# FEV-60_LED_Panel.net
KiCad netlist of a schematic drawn in Altium Designer
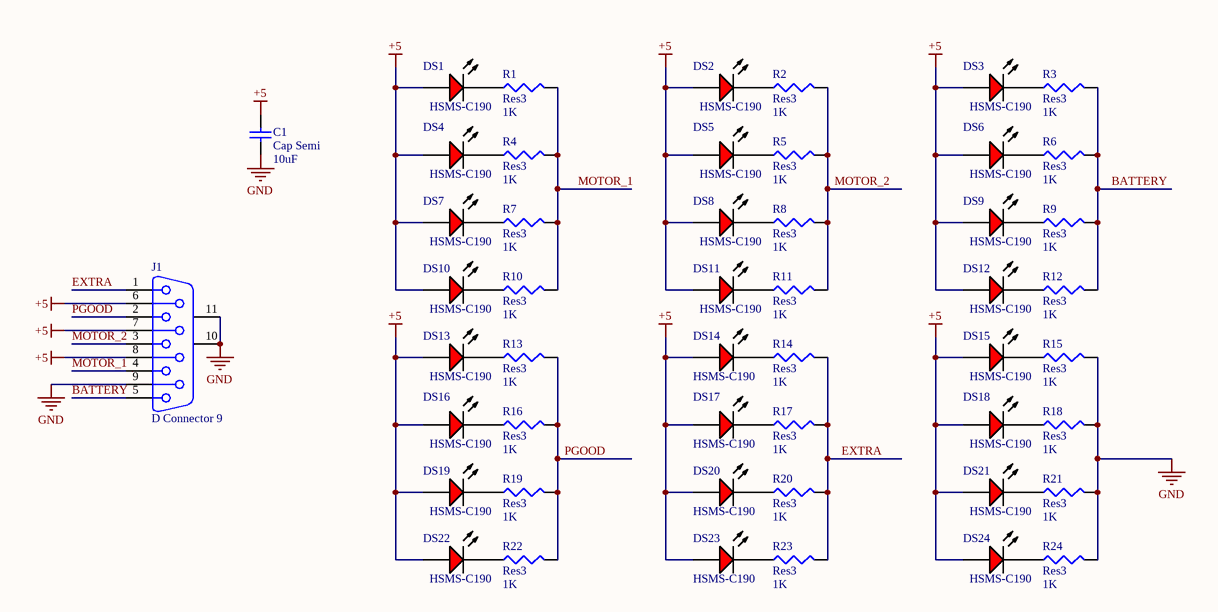
[diagram p0: FEV-60_LED_Panel.SchDoc]

(export (version "E")
  (design (tool "Eeschema 10.0.6"))
  (components
    (comp (ref "C1")
      (value "Cap Semi")
      (footprint "1608[0603]")
      (description "Capacitor (Semiconductor SIM Model)")
      (fields (field (name "ALTIUM_VALUE") "10uF") (field (name "PUBLISHER") "Altium Limited"))
      (libsource (lib "Miscellaneous Devices") (part "Cap Semi"))
    )
    (comp (ref "DS1")
      (value "HSMS-C190")
      (footprint "AVAG-HSMX-C190_V")
      (description "LED Uni-Color Red, 52 mW, 20 mA, -40 to 85 degC, 2-Pin SMD, RoHS, Tape and Reel")
      (fields (field (name "MANUFACTURER") "Avago"))
      (libsource (lib "Altium Content Vault") (part "LED-RED-AK-2"))
    )
    (comp (ref "DS2")
      (value "HSMS-C190")
      (footprint "AVAG-HSMX-C190_V")
      (description "LED Uni-Color Red, 52 mW, 20 mA, -40 to 85 degC, 2-Pin SMD, RoHS, Tape and Reel")
      (fields (field (name "MANUFACTURER") "Avago"))
      (libsource (lib "Altium Content Vault") (part "LED-RED-AK-2"))
    )
    (comp (ref "DS3")
      (value "HSMS-C190")
      (footprint "AVAG-HSMX-C190_V")
      (description "LED Uni-Color Red, 52 mW, 20 mA, -40 to 85 degC, 2-Pin SMD, RoHS, Tape and Reel")
      (fields (field (name "MANUFACTURER") "Avago"))
      (libsource (lib "Altium Content Vault") (part "LED-RED-AK-2"))
    )
    (comp (ref "DS4")
      (value "HSMS-C190")
      (footprint "AVAG-HSMX-C190_V")
      (description "LED Uni-Color Red, 52 mW, 20 mA, -40 to 85 degC, 2-Pin SMD, RoHS, Tape and Reel")
      (fields (field (name "MANUFACTURER") "Avago"))
      (libsource (lib "Altium Content Vault") (part "LED-RED-AK-2"))
    )
    (comp (ref "DS5")
      (value "HSMS-C190")
      (footprint "AVAG-HSMX-C190_V")
      (description "LED Uni-Color Red, 52 mW, 20 mA, -40 to 85 degC, 2-Pin SMD, RoHS, Tape and Reel")
      (fields (field (name "MANUFACTURER") "Avago"))
      (libsource (lib "Altium Content Vault") (part "LED-RED-AK-2"))
    )
    (comp (ref "DS6")
      (value "HSMS-C190")
      (footprint "AVAG-HSMX-C190_V")
      (description "LED Uni-Color Red, 52 mW, 20 mA, -40 to 85 degC, 2-Pin SMD, RoHS, Tape and Reel")
      (fields (field (name "MANUFACTURER") "Avago"))
      (libsource (lib "Altium Content Vault") (part "LED-RED-AK-2"))
    )
    (comp (ref "DS7")
      (value "HSMS-C190")
      (footprint "AVAG-HSMX-C190_V")
      (description "LED Uni-Color Red, 52 mW, 20 mA, -40 to 85 degC, 2-Pin SMD, RoHS, Tape and Reel")
      (fields (field (name "MANUFACTURER") "Avago"))
      (libsource (lib "Altium Content Vault") (part "LED-RED-AK-2"))
    )
    (comp (ref "DS8")
      (value "HSMS-C190")
      (footprint "AVAG-HSMX-C190_V")
      (description "LED Uni-Color Red, 52 mW, 20 mA, -40 to 85 degC, 2-Pin SMD, RoHS, Tape and Reel")
      (fields (field (name "MANUFACTURER") "Avago"))
      (libsource (lib "Altium Content Vault") (part "LED-RED-AK-2"))
    )
    (comp (ref "DS9")
      (value "HSMS-C190")
      (footprint "AVAG-HSMX-C190_V")
      (description "LED Uni-Color Red, 52 mW, 20 mA, -40 to 85 degC, 2-Pin SMD, RoHS, Tape and Reel")
      (fields (field (name "MANUFACTURER") "Avago"))
      (libsource (lib "Altium Content Vault") (part "LED-RED-AK-2"))
    )
    (comp (ref "DS10")
      (value "HSMS-C190")
      (footprint "AVAG-HSMX-C190_V")
      (description "LED Uni-Color Red, 52 mW, 20 mA, -40 to 85 degC, 2-Pin SMD, RoHS, Tape and Reel")
      (fields (field (name "MANUFACTURER") "Avago"))
      (libsource (lib "Altium Content Vault") (part "LED-RED-AK-2"))
    )
    (comp (ref "DS11")
      (value "HSMS-C190")
      (footprint "AVAG-HSMX-C190_V")
      (description "LED Uni-Color Red, 52 mW, 20 mA, -40 to 85 degC, 2-Pin SMD, RoHS, Tape and Reel")
      (fields (field (name "MANUFACTURER") "Avago"))
      (libsource (lib "Altium Content Vault") (part "LED-RED-AK-2"))
    )
    (comp (ref "DS12")
      (value "HSMS-C190")
      (footprint "AVAG-HSMX-C190_V")
      (description "LED Uni-Color Red, 52 mW, 20 mA, -40 to 85 degC, 2-Pin SMD, RoHS, Tape and Reel")
      (fields (field (name "MANUFACTURER") "Avago"))
      (libsource (lib "Altium Content Vault") (part "LED-RED-AK-2"))
    )
    (comp (ref "DS13")
      (value "HSMS-C190")
      (footprint "AVAG-HSMX-C190_V")
      (description "LED Uni-Color Red, 52 mW, 20 mA, -40 to 85 degC, 2-Pin SMD, RoHS, Tape and Reel")
      (fields (field (name "MANUFACTURER") "Avago"))
      (libsource (lib "Altium Content Vault") (part "LED-RED-AK-2"))
    )
    (comp (ref "DS14")
      (value "HSMS-C190")
      (footprint "AVAG-HSMX-C190_V")
      (description "LED Uni-Color Red, 52 mW, 20 mA, -40 to 85 degC, 2-Pin SMD, RoHS, Tape and Reel")
      (fields (field (name "MANUFACTURER") "Avago"))
      (libsource (lib "Altium Content Vault") (part "LED-RED-AK-2"))
    )
    (comp (ref "DS15")
      (value "HSMS-C190")
      (footprint "AVAG-HSMX-C190_V")
      (description "LED Uni-Color Red, 52 mW, 20 mA, -40 to 85 degC, 2-Pin SMD, RoHS, Tape and Reel")
      (fields (field (name "MANUFACTURER") "Avago"))
      (libsource (lib "Altium Content Vault") (part "LED-RED-AK-2"))
    )
    (comp (ref "DS16")
      (value "HSMS-C190")
      (footprint "AVAG-HSMX-C190_V")
      (description "LED Uni-Color Red, 52 mW, 20 mA, -40 to 85 degC, 2-Pin SMD, RoHS, Tape and Reel")
      (fields (field (name "MANUFACTURER") "Avago"))
      (libsource (lib "Altium Content Vault") (part "LED-RED-AK-2"))
    )
    (comp (ref "DS17")
      (value "HSMS-C190")
      (footprint "AVAG-HSMX-C190_V")
      (description "LED Uni-Color Red, 52 mW, 20 mA, -40 to 85 degC, 2-Pin SMD, RoHS, Tape and Reel")
      (fields (field (name "MANUFACTURER") "Avago"))
      (libsource (lib "Altium Content Vault") (part "LED-RED-AK-2"))
    )
    (comp (ref "DS18")
      (value "HSMS-C190")
      (footprint "AVAG-HSMX-C190_V")
      (description "LED Uni-Color Red, 52 mW, 20 mA, -40 to 85 degC, 2-Pin SMD, RoHS, Tape and Reel")
      (fields (field (name "MANUFACTURER") "Avago"))
      (libsource (lib "Altium Content Vault") (part "LED-RED-AK-2"))
    )
    (comp (ref "DS19")
      (value "HSMS-C190")
      (footprint "AVAG-HSMX-C190_V")
      (description "LED Uni-Color Red, 52 mW, 20 mA, -40 to 85 degC, 2-Pin SMD, RoHS, Tape and Reel")
      (fields (field (name "MANUFACTURER") "Avago"))
      (libsource (lib "Altium Content Vault") (part "LED-RED-AK-2"))
    )
    (comp (ref "DS20")
      (value "HSMS-C190")
      (footprint "AVAG-HSMX-C190_V")
      (description "LED Uni-Color Red, 52 mW, 20 mA, -40 to 85 degC, 2-Pin SMD, RoHS, Tape and Reel")
      (fields (field (name "MANUFACTURER") "Avago"))
      (libsource (lib "Altium Content Vault") (part "LED-RED-AK-2"))
    )
    (comp (ref "DS21")
      (value "HSMS-C190")
      (footprint "AVAG-HSMX-C190_V")
      (description "LED Uni-Color Red, 52 mW, 20 mA, -40 to 85 degC, 2-Pin SMD, RoHS, Tape and Reel")
      (fields (field (name "MANUFACTURER") "Avago"))
      (libsource (lib "Altium Content Vault") (part "LED-RED-AK-2"))
    )
    (comp (ref "DS22")
      (value "HSMS-C190")
      (footprint "AVAG-HSMX-C190_V")
      (description "LED Uni-Color Red, 52 mW, 20 mA, -40 to 85 degC, 2-Pin SMD, RoHS, Tape and Reel")
      (fields (field (name "MANUFACTURER") "Avago"))
      (libsource (lib "Altium Content Vault") (part "LED-RED-AK-2"))
    )
    (comp (ref "DS23")
      (value "HSMS-C190")
      (footprint "AVAG-HSMX-C190_V")
      (description "LED Uni-Color Red, 52 mW, 20 mA, -40 to 85 degC, 2-Pin SMD, RoHS, Tape and Reel")
      (fields (field (name "MANUFACTURER") "Avago"))
      (libsource (lib "Altium Content Vault") (part "LED-RED-AK-2"))
    )
    (comp (ref "DS24")
      (value "HSMS-C190")
      (footprint "AVAG-HSMX-C190_V")
      (description "LED Uni-Color Red, 52 mW, 20 mA, -40 to 85 degC, 2-Pin SMD, RoHS, Tape and Reel")
      (fields (field (name "MANUFACTURER") "Avago"))
      (libsource (lib "Altium Content Vault") (part "LED-RED-AK-2"))
    )
    (comp (ref "J1")
      (value "D Connector 9")
      (footprint "DSUB1.385-2H9")
      (description "Receptacle Assembly, 9 Position, Right Angle")
      (fields (field (name "PUBLISHER") "Altium Limited"))
      (libsource (lib "Miscellaneous Connectors") (part "D Connector 9"))
    )
    (comp (ref "R1")
      (value "Res3")
      (footprint "J1-0603")
      (description "Resistor")
      (fields (field (name "ALTIUM_VALUE") "1K") (field (name "PUBLISHER") "Altium Limited"))
      (libsource (lib "Miscellaneous Devices") (part "Res3"))
    )
    (comp (ref "R2")
      (value "Res3")
      (footprint "J1-0603")
      (description "Resistor")
      (fields (field (name "ALTIUM_VALUE") "1K") (field (name "PUBLISHER") "Altium Limited"))
      (libsource (lib "Miscellaneous Devices") (part "Res3"))
    )
    (comp (ref "R3")
      (value "Res3")
      (footprint "J1-0603")
      (description "Resistor")
      (fields (field (name "ALTIUM_VALUE") "1K") (field (name "PUBLISHER") "Altium Limited"))
      (libsource (lib "Miscellaneous Devices") (part "Res3"))
    )
    (comp (ref "R4")
      (value "Res3")
      (footprint "J1-0603")
      (description "Resistor")
      (fields (field (name "ALTIUM_VALUE") "1K") (field (name "PUBLISHER") "Altium Limited"))
      (libsource (lib "Miscellaneous Devices") (part "Res3"))
    )
    (comp (ref "R5")
      (value "Res3")
      (footprint "J1-0603")
      (description "Resistor")
      (fields (field (name "ALTIUM_VALUE") "1K") (field (name "PUBLISHER") "Altium Limited"))
      (libsource (lib "Miscellaneous Devices") (part "Res3"))
    )
    (comp (ref "R6")
      (value "Res3")
      (footprint "J1-0603")
      (description "Resistor")
      (fields (field (name "ALTIUM_VALUE") "1K") (field (name "PUBLISHER") "Altium Limited"))
      (libsource (lib "Miscellaneous Devices") (part "Res3"))
    )
    (comp (ref "R7")
      (value "Res3")
      (footprint "J1-0603")
      (description "Resistor")
      (fields (field (name "ALTIUM_VALUE") "1K") (field (name "PUBLISHER") "Altium Limited"))
      (libsource (lib "Miscellaneous Devices") (part "Res3"))
    )
    (comp (ref "R8")
      (value "Res3")
      (footprint "J1-0603")
      (description "Resistor")
      (fields (field (name "ALTIUM_VALUE") "1K") (field (name "PUBLISHER") "Altium Limited"))
      (libsource (lib "Miscellaneous Devices") (part "Res3"))
    )
    (comp (ref "R9")
      (value "Res3")
      (footprint "J1-0603")
      (description "Resistor")
      (fields (field (name "ALTIUM_VALUE") "1K") (field (name "PUBLISHER") "Altium Limited"))
      (libsource (lib "Miscellaneous Devices") (part "Res3"))
    )
    (comp (ref "R10")
      (value "Res3")
      (footprint "J1-0603")
      (description "Resistor")
      (fields (field (name "ALTIUM_VALUE") "1K") (field (name "PUBLISHER") "Altium Limited"))
      (libsource (lib "Miscellaneous Devices") (part "Res3"))
    )
    (comp (ref "R11")
      (value "Res3")
      (footprint "J1-0603")
      (description "Resistor")
      (fields (field (name "ALTIUM_VALUE") "1K") (field (name "PUBLISHER") "Altium Limited"))
      (libsource (lib "Miscellaneous Devices") (part "Res3"))
    )
    (comp (ref "R12")
      (value "Res3")
      (footprint "J1-0603")
      (description "Resistor")
      (fields (field (name "ALTIUM_VALUE") "1K") (field (name "PUBLISHER") "Altium Limited"))
      (libsource (lib "Miscellaneous Devices") (part "Res3"))
    )
    (comp (ref "R13")
      (value "Res3")
      (footprint "J1-0603")
      (description "Resistor")
      (fields (field (name "ALTIUM_VALUE") "1K") (field (name "PUBLISHER") "Altium Limited"))
      (libsource (lib "Miscellaneous Devices") (part "Res3"))
    )
    (comp (ref "R14")
      (value "Res3")
      (footprint "J1-0603")
      (description "Resistor")
      (fields (field (name "ALTIUM_VALUE") "1K") (field (name "PUBLISHER") "Altium Limited"))
      (libsource (lib "Miscellaneous Devices") (part "Res3"))
    )
    (comp (ref "R15")
      (value "Res3")
      (footprint "J1-0603")
      (description "Resistor")
      (fields (field (name "ALTIUM_VALUE") "1K") (field (name "PUBLISHER") "Altium Limited"))
      (libsource (lib "Miscellaneous Devices") (part "Res3"))
    )
    (comp (ref "R16")
      (value "Res3")
      (footprint "J1-0603")
      (description "Resistor")
      (fields (field (name "ALTIUM_VALUE") "1K") (field (name "PUBLISHER") "Altium Limited"))
      (libsource (lib "Miscellaneous Devices") (part "Res3"))
    )
    (comp (ref "R17")
      (value "Res3")
      (footprint "J1-0603")
      (description "Resistor")
      (fields (field (name "ALTIUM_VALUE") "1K") (field (name "PUBLISHER") "Altium Limited"))
      (libsource (lib "Miscellaneous Devices") (part "Res3"))
    )
    (comp (ref "R18")
      (value "Res3")
      (footprint "J1-0603")
      (description "Resistor")
      (fields (field (name "ALTIUM_VALUE") "1K") (field (name "PUBLISHER") "Altium Limited"))
      (libsource (lib "Miscellaneous Devices") (part "Res3"))
    )
    (comp (ref "R19")
      (value "Res3")
      (footprint "J1-0603")
      (description "Resistor")
      (fields (field (name "ALTIUM_VALUE") "1K") (field (name "PUBLISHER") "Altium Limited"))
      (libsource (lib "Miscellaneous Devices") (part "Res3"))
    )
    (comp (ref "R20")
      (value "Res3")
      (footprint "J1-0603")
      (description "Resistor")
      (fields (field (name "ALTIUM_VALUE") "1K") (field (name "PUBLISHER") "Altium Limited"))
      (libsource (lib "Miscellaneous Devices") (part "Res3"))
    )
    (comp (ref "R21")
      (value "Res3")
      (footprint "J1-0603")
      (description "Resistor")
      (fields (field (name "ALTIUM_VALUE") "1K") (field (name "PUBLISHER") "Altium Limited"))
      (libsource (lib "Miscellaneous Devices") (part "Res3"))
    )
    (comp (ref "R22")
      (value "Res3")
      (footprint "J1-0603")
      (description "Resistor")
      (fields (field (name "ALTIUM_VALUE") "1K") (field (name "PUBLISHER") "Altium Limited"))
      (libsource (lib "Miscellaneous Devices") (part "Res3"))
    )
    (comp (ref "R23")
      (value "Res3")
      (footprint "J1-0603")
      (description "Resistor")
      (fields (field (name "ALTIUM_VALUE") "1K") (field (name "PUBLISHER") "Altium Limited"))
      (libsource (lib "Miscellaneous Devices") (part "Res3"))
    )
    (comp (ref "R24")
      (value "Res3")
      (footprint "J1-0603")
      (description "Resistor")
      (fields (field (name "ALTIUM_VALUE") "1K") (field (name "PUBLISHER") "Altium Limited"))
      (libsource (lib "Miscellaneous Devices") (part "Res3"))
    )
  )
  (nets
    (net (code "1") (name "+5") (class "Default")
      (node (ref "C1") (pin "2") (pinfunction "2_2") (pintype "passive"))
      (node (ref "DS1") (pin "1") (pinfunction "A_1") (pintype "passive"))
      (node (ref "DS10") (pin "1") (pinfunction "A_1") (pintype "passive"))
      (node (ref "DS11") (pin "1") (pinfunction "A_1") (pintype "passive"))
      (node (ref "DS12") (pin "1") (pinfunction "A_1") (pintype "passive"))
      (node (ref "DS13") (pin "1") (pinfunction "A_1") (pintype "passive"))
      (node (ref "DS14") (pin "1") (pinfunction "A_1") (pintype "passive"))
      (node (ref "DS15") (pin "1") (pinfunction "A_1") (pintype "passive"))
      (node (ref "DS16") (pin "1") (pinfunction "A_1") (pintype "passive"))
      (node (ref "DS17") (pin "1") (pinfunction "A_1") (pintype "passive"))
      (node (ref "DS18") (pin "1") (pinfunction "A_1") (pintype "passive"))
      (node (ref "DS19") (pin "1") (pinfunction "A_1") (pintype "passive"))
      (node (ref "DS2") (pin "1") (pinfunction "A_1") (pintype "passive"))
      (node (ref "DS20") (pin "1") (pinfunction "A_1") (pintype "passive"))
      (node (ref "DS21") (pin "1") (pinfunction "A_1") (pintype "passive"))
      (node (ref "DS22") (pin "1") (pinfunction "A_1") (pintype "passive"))
      (node (ref "DS23") (pin "1") (pinfunction "A_1") (pintype "passive"))
      (node (ref "DS24") (pin "1") (pinfunction "A_1") (pintype "passive"))
      (node (ref "DS3") (pin "1") (pinfunction "A_1") (pintype "passive"))
      (node (ref "DS4") (pin "1") (pinfunction "A_1") (pintype "passive"))
      (node (ref "DS5") (pin "1") (pinfunction "A_1") (pintype "passive"))
      (node (ref "DS6") (pin "1") (pinfunction "A_1") (pintype "passive"))
      (node (ref "DS7") (pin "1") (pinfunction "A_1") (pintype "passive"))
      (node (ref "DS8") (pin "1") (pinfunction "A_1") (pintype "passive"))
      (node (ref "DS9") (pin "1") (pinfunction "A_1") (pintype "passive"))
      (node (ref "J1") (pin "6") (pinfunction "6_6") (pintype "passive"))
      (node (ref "J1") (pin "7") (pinfunction "7_7") (pintype "passive"))
      (node (ref "J1") (pin "8") (pinfunction "8_8") (pintype "passive"))
    )
    (net (code "2") (name "/BATTERY") (class "Default")
      (node (ref "J1") (pin "5") (pinfunction "5_5") (pintype "passive"))
      (node (ref "R12") (pin "2") (pinfunction "2_2") (pintype "passive"))
      (node (ref "R3") (pin "2") (pinfunction "2_2") (pintype "passive"))
      (node (ref "R6") (pin "2") (pinfunction "2_2") (pintype "passive"))
      (node (ref "R9") (pin "2") (pinfunction "2_2") (pintype "passive"))
    )
    (net (code "3") (name "/EXTRA") (class "Default")
      (node (ref "J1") (pin "1") (pinfunction "1_1") (pintype "passive"))
      (node (ref "R14") (pin "2") (pinfunction "2_2") (pintype "passive"))
      (node (ref "R17") (pin "2") (pinfunction "2_2") (pintype "passive"))
      (node (ref "R20") (pin "2") (pinfunction "2_2") (pintype "passive"))
      (node (ref "R23") (pin "2") (pinfunction "2_2") (pintype "passive"))
    )
    (net (code "4") (name "/MOTOR_1") (class "Default")
      (node (ref "J1") (pin "4") (pinfunction "4_4") (pintype "passive"))
      (node (ref "R1") (pin "2") (pinfunction "2_2") (pintype "passive"))
      (node (ref "R10") (pin "2") (pinfunction "2_2") (pintype "passive"))
      (node (ref "R4") (pin "2") (pinfunction "2_2") (pintype "passive"))
      (node (ref "R7") (pin "2") (pinfunction "2_2") (pintype "passive"))
    )
    (net (code "5") (name "/MOTOR_2") (class "Default")
      (node (ref "J1") (pin "3") (pinfunction "3_3") (pintype "passive"))
      (node (ref "R11") (pin "2") (pinfunction "2_2") (pintype "passive"))
      (node (ref "R2") (pin "2") (pinfunction "2_2") (pintype "passive"))
      (node (ref "R5") (pin "2") (pinfunction "2_2") (pintype "passive"))
      (node (ref "R8") (pin "2") (pinfunction "2_2") (pintype "passive"))
    )
    (net (code "6") (name "/PGOOD") (class "Default")
      (node (ref "J1") (pin "2") (pinfunction "2_2") (pintype "passive"))
      (node (ref "R13") (pin "2") (pinfunction "2_2") (pintype "passive"))
      (node (ref "R16") (pin "2") (pinfunction "2_2") (pintype "passive"))
      (node (ref "R19") (pin "2") (pinfunction "2_2") (pintype "passive"))
      (node (ref "R22") (pin "2") (pinfunction "2_2") (pintype "passive"))
    )
    (net (code "7") (name "GND") (class "Default")
      (node (ref "C1") (pin "1") (pinfunction "1_1") (pintype "passive"))
      (node (ref "J1") (pin "10") (pinfunction "MH1_10") (pintype "passive"))
      (node (ref "J1") (pin "11") (pinfunction "MH2_11") (pintype "passive"))
      (node (ref "J1") (pin "9") (pinfunction "9_9") (pintype "passive"))
      (node (ref "R15") (pin "2") (pinfunction "2_2") (pintype "passive"))
      (node (ref "R18") (pin "2") (pinfunction "2_2") (pintype "passive"))
      (node (ref "R21") (pin "2") (pinfunction "2_2") (pintype "passive"))
      (node (ref "R24") (pin "2") (pinfunction "2_2") (pintype "passive"))
    )
    (net (code "8") (name "Net-(DS1-K)") (class "Default")
      (node (ref "DS1") (pin "2") (pinfunction "K_2") (pintype "passive"))
      (node (ref "R1") (pin "1") (pinfunction "1_1") (pintype "passive"))
    )
    (net (code "9") (name "Net-(DS2-K)") (class "Default")
      (node (ref "DS2") (pin "2") (pinfunction "K_2") (pintype "passive"))
      (node (ref "R2") (pin "1") (pinfunction "1_1") (pintype "passive"))
    )
    (net (code "10") (name "Net-(DS3-K)") (class "Default")
      (node (ref "DS3") (pin "2") (pinfunction "K_2") (pintype "passive"))
      (node (ref "R3") (pin "1") (pinfunction "1_1") (pintype "passive"))
    )
    (net (code "11") (name "Net-(DS4-K)") (class "Default")
      (node (ref "DS4") (pin "2") (pinfunction "K_2") (pintype "passive"))
      (node (ref "R4") (pin "1") (pinfunction "1_1") (pintype "passive"))
    )
    (net (code "12") (name "Net-(DS5-K)") (class "Default")
      (node (ref "DS5") (pin "2") (pinfunction "K_2") (pintype "passive"))
      (node (ref "R5") (pin "1") (pinfunction "1_1") (pintype "passive"))
    )
    (net (code "13") (name "Net-(DS6-K)") (class "Default")
      (node (ref "DS6") (pin "2") (pinfunction "K_2") (pintype "passive"))
      (node (ref "R6") (pin "1") (pinfunction "1_1") (pintype "passive"))
    )
    (net (code "14") (name "Net-(DS7-K)") (class "Default")
      (node (ref "DS7") (pin "2") (pinfunction "K_2") (pintype "passive"))
      (node (ref "R7") (pin "1") (pinfunction "1_1") (pintype "passive"))
    )
    (net (code "15") (name "Net-(DS8-K)") (class "Default")
      (node (ref "DS8") (pin "2") (pinfunction "K_2") (pintype "passive"))
      (node (ref "R8") (pin "1") (pinfunction "1_1") (pintype "passive"))
    )
    (net (code "16") (name "Net-(DS9-K)") (class "Default")
      (node (ref "DS9") (pin "2") (pinfunction "K_2") (pintype "passive"))
      (node (ref "R9") (pin "1") (pinfunction "1_1") (pintype "passive"))
    )
    (net (code "17") (name "Net-(DS10-K)") (class "Default")
      (node (ref "DS10") (pin "2") (pinfunction "K_2") (pintype "passive"))
      (node (ref "R10") (pin "1") (pinfunction "1_1") (pintype "passive"))
    )
    (net (code "18") (name "Net-(DS11-K)") (class "Default")
      (node (ref "DS11") (pin "2") (pinfunction "K_2") (pintype "passive"))
      (node (ref "R11") (pin "1") (pinfunction "1_1") (pintype "passive"))
    )
    (net (code "19") (name "Net-(DS12-K)") (class "Default")
      (node (ref "DS12") (pin "2") (pinfunction "K_2") (pintype "passive"))
      (node (ref "R12") (pin "1") (pinfunction "1_1") (pintype "passive"))
    )
    (net (code "20") (name "Net-(DS13-K)") (class "Default")
      (node (ref "DS13") (pin "2") (pinfunction "K_2") (pintype "passive"))
      (node (ref "R13") (pin "1") (pinfunction "1_1") (pintype "passive"))
    )
    (net (code "21") (name "Net-(DS14-K)") (class "Default")
      (node (ref "DS14") (pin "2") (pinfunction "K_2") (pintype "passive"))
      (node (ref "R14") (pin "1") (pinfunction "1_1") (pintype "passive"))
    )
    (net (code "22") (name "Net-(DS15-K)") (class "Default")
      (node (ref "DS15") (pin "2") (pinfunction "K_2") (pintype "passive"))
      (node (ref "R15") (pin "1") (pinfunction "1_1") (pintype "passive"))
    )
    (net (code "23") (name "Net-(DS16-K)") (class "Default")
      (node (ref "DS16") (pin "2") (pinfunction "K_2") (pintype "passive"))
      (node (ref "R16") (pin "1") (pinfunction "1_1") (pintype "passive"))
    )
    (net (code "24") (name "Net-(DS17-K)") (class "Default")
      (node (ref "DS17") (pin "2") (pinfunction "K_2") (pintype "passive"))
      (node (ref "R17") (pin "1") (pinfunction "1_1") (pintype "passive"))
    )
    (net (code "25") (name "Net-(DS18-K)") (class "Default")
      (node (ref "DS18") (pin "2") (pinfunction "K_2") (pintype "passive"))
      (node (ref "R18") (pin "1") (pinfunction "1_1") (pintype "passive"))
    )
    (net (code "26") (name "Net-(DS19-K)") (class "Default")
      (node (ref "DS19") (pin "2") (pinfunction "K_2") (pintype "passive"))
      (node (ref "R19") (pin "1") (pinfunction "1_1") (pintype "passive"))
    )
    (net (code "27") (name "Net-(DS20-K)") (class "Default")
      (node (ref "DS20") (pin "2") (pinfunction "K_2") (pintype "passive"))
      (node (ref "R20") (pin "1") (pinfunction "1_1") (pintype "passive"))
    )
    (net (code "28") (name "Net-(DS21-K)") (class "Default")
      (node (ref "DS21") (pin "2") (pinfunction "K_2") (pintype "passive"))
      (node (ref "R21") (pin "1") (pinfunction "1_1") (pintype "passive"))
    )
    (net (code "29") (name "Net-(DS22-K)") (class "Default")
      (node (ref "DS22") (pin "2") (pinfunction "K_2") (pintype "passive"))
      (node (ref "R22") (pin "1") (pinfunction "1_1") (pintype "passive"))
    )
    (net (code "30") (name "Net-(DS23-K)") (class "Default")
      (node (ref "DS23") (pin "2") (pinfunction "K_2") (pintype "passive"))
      (node (ref "R23") (pin "1") (pinfunction "1_1") (pintype "passive"))
    )
    (net (code "31") (name "Net-(DS24-K)") (class "Default")
      (node (ref "DS24") (pin "2") (pinfunction "K_2") (pintype "passive"))
      (node (ref "R24") (pin "1") (pinfunction "1_1") (pintype "passive"))
    )
  )
)
